# 1_POWER.net
KiCad netlist of a schematic drawn in Altium Designer
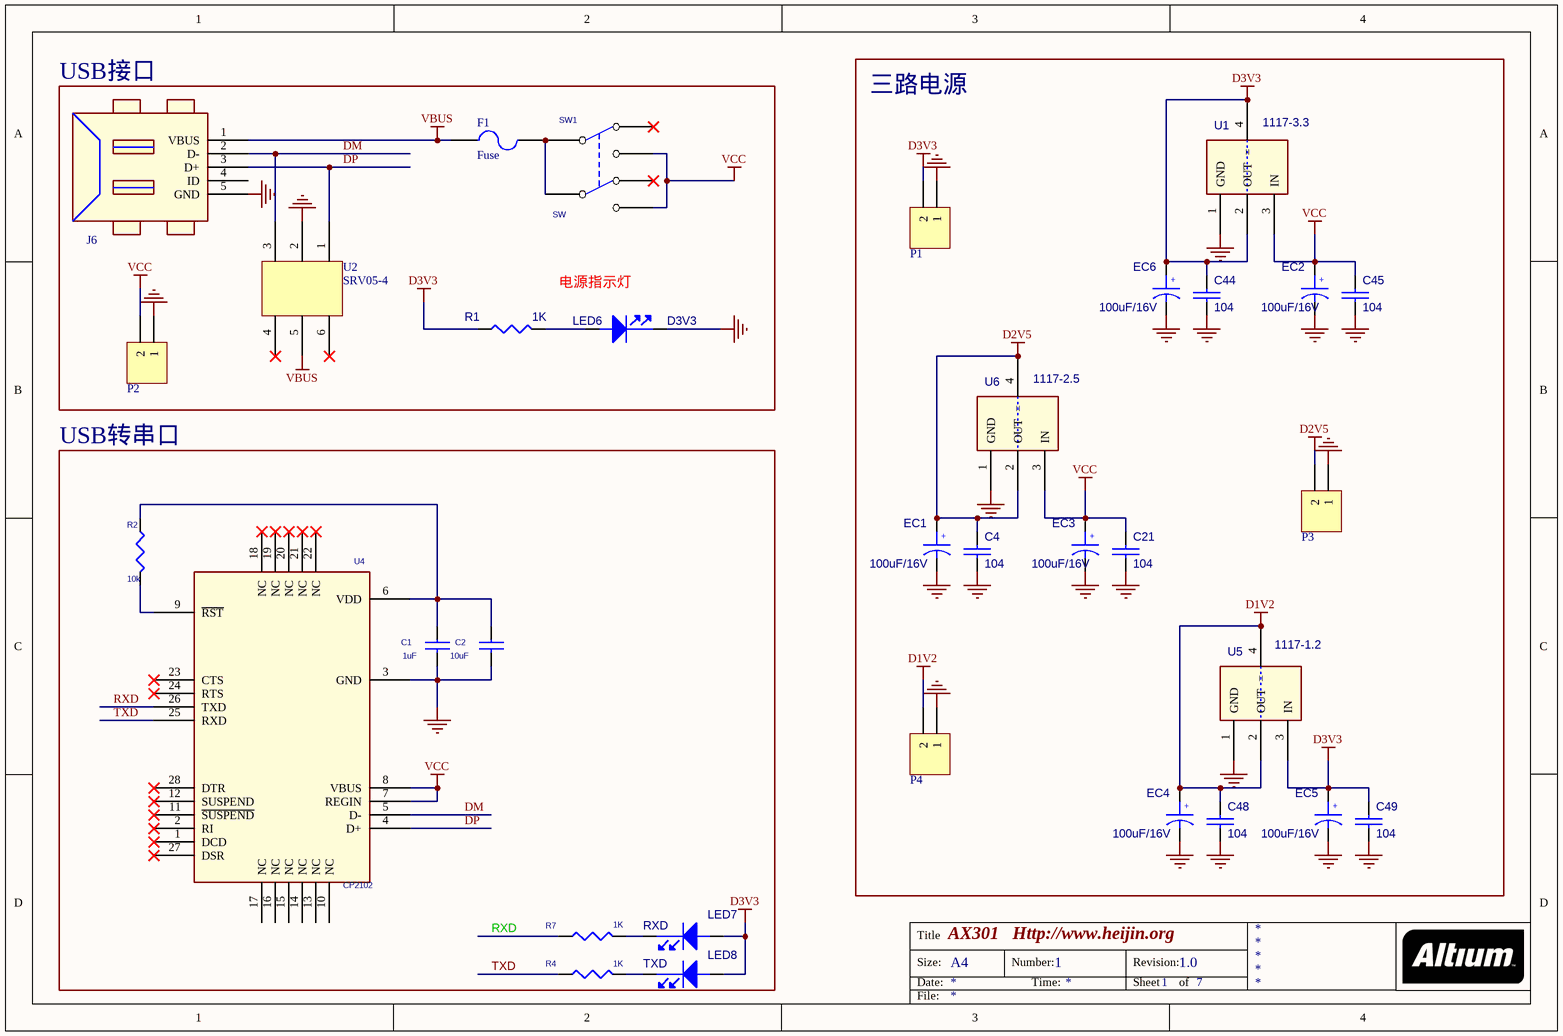
[diagram p0: 1_POWER.SchDoc]

(export (version "E")
  (design (tool "Eeschema 10.0.6"))
  (components
    (comp (ref "C1") (value "1uF") (libsource (lib "*") (part "CAP NP_Dup2")))
    (comp (ref "C2") (value "10uF") (libsource (lib "*") (part "CAP NP_Dup2")))
    (comp (ref "C4") (value "104") (libsource (lib "*") (part "C_Dup4")))
    (comp (ref "C21") (value "104") (libsource (lib "*") (part "C_Dup4")))
    (comp (ref "C44") (value "104") (libsource (lib "*") (part "C_Dup4")))
    (comp (ref "C45") (value "104") (libsource (lib "*") (part "C_Dup4")))
    (comp (ref "C48") (value "104") (libsource (lib "*") (part "C_Dup4")))
    (comp (ref "C49") (value "104") (libsource (lib "*") (part "C_Dup4")))
    (comp (ref "EC1") (value "100uF/16V") (libsource (lib "*") (part "EC")))
    (comp (ref "EC2") (value "100uF/16V") (libsource (lib "*") (part "EC")))
    (comp (ref "EC3") (value "100uF/16V") (libsource (lib "*") (part "EC")))
    (comp (ref "EC4") (value "100uF/16V") (libsource (lib "*") (part "EC")))
    (comp (ref "EC5") (value "100uF/16V") (libsource (lib "*") (part "EC")))
    (comp (ref "EC6") (value "100uF/16V") (libsource (lib "*") (part "EC")))
    (comp (ref "F1")
      (value "Fuse")
      (footprint "ALINX:1812")
      (fields (field (name "PUBLISHER") "Altium Limited"))
      (libsource (lib "Miscellaneous Devices") (part "Fuse 2"))
    )
    (comp (ref "J6") (value "EC2") (footprint "MINIUSBB") (libsource (lib "*") (part "MiniUSBB")))
    (comp (ref "LED6") (value "D3V3") (footprint "LEDSO") (libsource (lib "*") (part "LED_Dup1")))
    (comp (ref "LED7") (value "RXD") (footprint "LEDSO") (libsource (lib "*") (part "LED")))
    (comp (ref "LED8") (value "TXD") (footprint "LEDSO") (libsource (lib "*") (part "LED")))
    (comp (ref "P1")
      (value "3.3V")
      (footprint "HDR1X2")
      (description "Header, 2-Pin")
      (fields (field (name "PUBLISHER") "Altium Limited"))
      (libsource (lib "Miscellaneous Connectors") (part "Header 2"))
    )
    (comp (ref "P2")
      (value "5V")
      (footprint "HDR1X2")
      (description "Header, 2-Pin")
      (fields (field (name "PUBLISHER") "Altium Limited"))
      (libsource (lib "Miscellaneous Connectors") (part "Header 2"))
    )
    (comp (ref "P3")
      (value "3.3V")
      (footprint "HDR1X2")
      (description "Header, 2-Pin")
      (fields (field (name "PUBLISHER") "Altium Limited"))
      (libsource (lib "Miscellaneous Connectors") (part "Header 2"))
    )
    (comp (ref "P4")
      (value "1.2V")
      (footprint "HDR1X2")
      (description "Header, 2-Pin")
      (fields (field (name "PUBLISHER") "Altium Limited"))
      (libsource (lib "Miscellaneous Connectors") (part "Header 2"))
    )
    (comp (ref "R1") (value "1K") (footprint "0603") (libsource (lib "*") (part "R")))
    (comp (ref "R2") (value "10k") (libsource (lib "*") (part "RESISTOR")))
    (comp (ref "R4") (value "1K") (footprint "0603") (libsource (lib "*") (part "R_Dup3")))
    (comp (ref "R7") (value "1K") (footprint "0603") (libsource (lib "*") (part "R_Dup3")))
    (comp (ref "SW1") (value "SW") (libsource (lib "*") (part "SW KEY-DPDT")))
    (comp (ref "U1") (value "1117-3.3") (footprint "SOT223") (libsource (lib "*") (part "1117-3.3")))
    (comp (ref "U2")
      (value "SRV05-4")
      (footprint "wfj_pcb:SOT23-6")
      (libsource (lib "heijin") (part "SRV05-4"))
    )
    (comp (ref "U4") (value "CP2102") (libsource (lib "*") (part "CP2102_0")))
    (comp (ref "U5") (value "1117-1.2") (footprint "SOT223") (libsource (lib "*") (part "1117-3.3")))
    (comp (ref "U6") (value "1117-2.5") (footprint "SOT223") (libsource (lib "*") (part "1117-3.3")))
  )
  (nets
    (net (code "1") (name "/DM") (class "Default")
      (node (ref "J6") (pin "2") (pinfunction "D-_2") (pintype "passive"))
      (node (ref "U2") (pin "3") (pinfunction "3_3") (pintype "passive"))
      (node (ref "U4") (pin "5") (pinfunction "D-_5") (pintype "passive"))
    )
    (net (code "2") (name "/DP") (class "Default")
      (node (ref "J6") (pin "3") (pinfunction "D+_3") (pintype "passive"))
      (node (ref "U2") (pin "1") (pinfunction "1_1") (pintype "passive"))
      (node (ref "U4") (pin "4") (pinfunction "D+_4") (pintype "passive"))
    )
    (net (code "3") (name "/RXD") (class "Default")
      (node (ref "R7") (pin "1") (pinfunction "1_1") (pintype "passive"))
      (node (ref "U4") (pin "26") (pinfunction "TXD_26") (pintype "passive"))
    )
    (net (code "4") (name "/TXD") (class "Default")
      (node (ref "R4") (pin "1") (pinfunction "1_1") (pintype "passive"))
      (node (ref "U4") (pin "25") (pinfunction "RXD_25") (pintype "passive"))
    )
    (net (code "5") (name "D1V2") (class "Default")
      (node (ref "C48") (pin "1") (pinfunction "1_1") (pintype "passive"))
      (node (ref "EC4") (pin "1") (pinfunction "1_1") (pintype "passive"))
      (node (ref "P4") (pin "2") (pinfunction "2_2") (pintype "passive"))
      (node (ref "U5") (pin "2") (pinfunction "OUT_2") (pintype "passive"))
      (node (ref "U5") (pin "4") (pinfunction "=_4") (pintype "passive"))
    )
    (net (code "6") (name "D2V5") (class "Default")
      (node (ref "C4") (pin "1") (pinfunction "1_1") (pintype "passive"))
      (node (ref "EC1") (pin "1") (pinfunction "1_1") (pintype "passive"))
      (node (ref "P3") (pin "2") (pinfunction "2_2") (pintype "passive"))
      (node (ref "U6") (pin "2") (pinfunction "OUT_2") (pintype "passive"))
      (node (ref "U6") (pin "4") (pinfunction "=_4") (pintype "passive"))
    )
    (net (code "7") (name "D3V3") (class "Default")
      (node (ref "C44") (pin "1") (pinfunction "1_1") (pintype "passive"))
      (node (ref "C49") (pin "1") (pinfunction "1_1") (pintype "passive"))
      (node (ref "EC5") (pin "1") (pinfunction "1_1") (pintype "passive"))
      (node (ref "EC6") (pin "1") (pinfunction "1_1") (pintype "passive"))
      (node (ref "LED7") (pin "1") (pinfunction "ANODE_1") (pintype "passive"))
      (node (ref "LED8") (pin "1") (pinfunction "ANODE_1") (pintype "passive"))
      (node (ref "P1") (pin "2") (pinfunction "2_2") (pintype "passive"))
      (node (ref "R1") (pin "1") (pinfunction "1_1") (pintype "passive"))
      (node (ref "U1") (pin "2") (pinfunction "OUT_2") (pintype "passive"))
      (node (ref "U1") (pin "4") (pinfunction "=_4") (pintype "passive"))
      (node (ref "U5") (pin "3") (pinfunction "IN_3") (pintype "passive"))
    )
    (net (code "8") (name "GND") (class "Default")
      (node (ref "C1") (pin "2") (pinfunction "2_2") (pintype "passive"))
      (node (ref "C2") (pin "2") (pinfunction "2_2") (pintype "passive"))
      (node (ref "C21") (pin "2") (pinfunction "2_2") (pintype "passive"))
      (node (ref "C4") (pin "2") (pinfunction "2_2") (pintype "passive"))
      (node (ref "C44") (pin "2") (pinfunction "2_2") (pintype "passive"))
      (node (ref "C45") (pin "2") (pinfunction "2_2") (pintype "passive"))
      (node (ref "C48") (pin "2") (pinfunction "2_2") (pintype "passive"))
      (node (ref "C49") (pin "2") (pinfunction "2_2") (pintype "passive"))
      (node (ref "EC1") (pin "2") (pinfunction "2_2") (pintype "passive"))
      (node (ref "EC2") (pin "2") (pinfunction "2_2") (pintype "passive"))
      (node (ref "EC3") (pin "2") (pinfunction "2_2") (pintype "passive"))
      (node (ref "EC4") (pin "2") (pinfunction "2_2") (pintype "passive"))
      (node (ref "EC5") (pin "2") (pinfunction "2_2") (pintype "passive"))
      (node (ref "EC6") (pin "2") (pinfunction "2_2") (pintype "passive"))
      (node (ref "J6") (pin "5") (pinfunction "GND_5") (pintype "passive"))
      (node (ref "LED6") (pin "2") (pinfunction "CATHODE_2") (pintype "passive"))
      (node (ref "P1") (pin "1") (pinfunction "1_1") (pintype "passive"))
      (node (ref "P2") (pin "1") (pinfunction "1_1") (pintype "passive"))
      (node (ref "P3") (pin "1") (pinfunction "1_1") (pintype "passive"))
      (node (ref "P4") (pin "1") (pinfunction "1_1") (pintype "passive"))
      (node (ref "U1") (pin "1") (pinfunction "GND_1") (pintype "passive"))
      (node (ref "U2") (pin "2") (pinfunction "2_2") (pintype "passive"))
      (node (ref "U4") (pin "3") (pinfunction "GND_3") (pintype "power_in"))
      (node (ref "U5") (pin "1") (pinfunction "GND_1") (pintype "passive"))
      (node (ref "U6") (pin "1") (pinfunction "GND_1") (pintype "passive"))
    )
    (net (code "9") (name "Net-(LED6-ANODE)") (class "Default")
      (node (ref "LED6") (pin "1") (pinfunction "ANODE_1") (pintype "passive"))
      (node (ref "R1") (pin "2") (pinfunction "2_2") (pintype "passive"))
    )
    (net (code "10") (name "Net-(LED7-CATHODE)") (class "Default")
      (node (ref "LED7") (pin "2") (pinfunction "CATHODE_2") (pintype "passive"))
      (node (ref "R7") (pin "2") (pinfunction "2_2") (pintype "passive"))
    )
    (net (code "11") (name "Net-(LED8-CATHODE)") (class "Default")
      (node (ref "LED8") (pin "2") (pinfunction "CATHODE_2") (pintype "passive"))
      (node (ref "R4") (pin "2") (pinfunction "2_2") (pintype "passive"))
    )
    (net (code "12") (name "Net-(SW1-COMMON1)") (class "Default")
      (node (ref "F1") (pin "2") (pinfunction "2_2") (pintype "passive"))
      (node (ref "SW1") (pin "2") (pinfunction "COMMON1_2") (pintype "passive"))
      (node (ref "SW1") (pin "5") (pinfunction "COMMON2_5") (pintype "passive"))
    )
    (net (code "13") (name "Net-(U4-VDD)") (class "Default")
      (node (ref "C1") (pin "1") (pinfunction "1_1") (pintype "passive"))
      (node (ref "C2") (pin "1") (pinfunction "1_1") (pintype "passive"))
      (node (ref "R2") (pin "2") (pinfunction "2_2") (pintype "passive"))
      (node (ref "U4") (pin "6") (pinfunction "VDD_6") (pintype "power_in"))
    )
    (net (code "14") (name "Net-(U4-~{RST})") (class "Default")
      (node (ref "R2") (pin "1") (pinfunction "1_1") (pintype "passive"))
      (node (ref "U4") (pin "9") (pinfunction "~{RST}_9") (pintype "passive"))
    )
    (net (code "15") (name "VBUS") (class "Default")
      (node (ref "F1") (pin "1") (pinfunction "1_1") (pintype "passive"))
      (node (ref "J6") (pin "1") (pinfunction "VBUS_1") (pintype "passive"))
      (node (ref "U2") (pin "5") (pinfunction "5_5") (pintype "passive"))
    )
    (net (code "16") (name "VCC") (class "Default")
      (node (ref "C21") (pin "1") (pinfunction "1_1") (pintype "passive"))
      (node (ref "C45") (pin "1") (pinfunction "1_1") (pintype "passive"))
      (node (ref "EC2") (pin "1") (pinfunction "1_1") (pintype "passive"))
      (node (ref "EC3") (pin "1") (pinfunction "1_1") (pintype "passive"))
      (node (ref "P2") (pin "2") (pinfunction "2_2") (pintype "passive"))
      (node (ref "SW1") (pin "3") (pinfunction "NO1_3") (pintype "passive"))
      (node (ref "SW1") (pin "6") (pinfunction "NO2_6") (pintype "passive"))
      (node (ref "U1") (pin "3") (pinfunction "IN_3") (pintype "passive"))
      (node (ref "U4") (pin "7") (pinfunction "REGIN_7") (pintype "passive"))
      (node (ref "U4") (pin "8") (pinfunction "VBUS_8") (pintype "passive"))
      (node (ref "U6") (pin "3") (pinfunction "IN_3") (pintype "passive"))
    )
    (net (code "17") (name "unconnected-(J6-ID-Pad4)") (class "Default")
      (node (ref "J6") (pin "4") (pinfunction "ID_4") (pintype "passive"))
    )
    (net (code "18") (name "unconnected-(SW1-NC1-Pad1)") (class "Default")
      (node (ref "SW1") (pin "1") (pinfunction "NC1_1") (pintype "passive+no_connect"))
    )
    (net (code "19") (name "unconnected-(SW1-NC2-Pad4)") (class "Default")
      (node (ref "SW1") (pin "4") (pinfunction "NC2_4") (pintype "passive+no_connect"))
    )
    (net (code "20") (name "unconnected-(U2-Pad4)") (class "Default")
      (node (ref "U2") (pin "4") (pinfunction "4_4") (pintype "passive+no_connect"))
    )
    (net (code "21") (name "unconnected-(U2-Pad6)") (class "Default")
      (node (ref "U2") (pin "6") (pinfunction "6_6") (pintype "passive+no_connect"))
    )
    (net (code "22") (name "unconnected-(U4-CTS-Pad23)") (class "Default")
      (node (ref "U4") (pin "23") (pinfunction "CTS_23") (pintype "passive+no_connect"))
    )
    (net (code "23") (name "unconnected-(U4-DCD-Pad1)") (class "Default")
      (node (ref "U4") (pin "1") (pinfunction "DCD_1") (pintype "passive+no_connect"))
    )
    (net (code "24") (name "unconnected-(U4-DSR-Pad27)") (class "Default")
      (node (ref "U4") (pin "27") (pinfunction "DSR_27") (pintype "passive+no_connect"))
    )
    (net (code "25") (name "unconnected-(U4-DTR-Pad28)") (class "Default")
      (node (ref "U4") (pin "28") (pinfunction "DTR_28") (pintype "passive+no_connect"))
    )
    (net (code "26") (name "unconnected-(U4-NC-Pad10)") (class "Default")
      (node (ref "U4") (pin "10") (pinfunction "NC_10") (pintype "passive"))
    )
    (net (code "27") (name "unconnected-(U4-NC-Pad13)") (class "Default")
      (node (ref "U4") (pin "13") (pinfunction "NC_13") (pintype "passive"))
    )
    (net (code "28") (name "unconnected-(U4-NC-Pad14)") (class "Default")
      (node (ref "U4") (pin "14") (pinfunction "NC_14") (pintype "passive"))
    )
    (net (code "29") (name "unconnected-(U4-NC-Pad15)") (class "Default")
      (node (ref "U4") (pin "15") (pinfunction "NC_15") (pintype "passive"))
    )
    (net (code "30") (name "unconnected-(U4-NC-Pad16)") (class "Default")
      (node (ref "U4") (pin "16") (pinfunction "NC_16") (pintype "passive"))
    )
    (net (code "31") (name "unconnected-(U4-NC-Pad17)") (class "Default")
      (node (ref "U4") (pin "17") (pinfunction "NC_17") (pintype "passive"))
    )
    (net (code "32") (name "unconnected-(U4-NC-Pad18)") (class "Default")
      (node (ref "U4") (pin "18") (pinfunction "NC_18") (pintype "passive+no_connect"))
    )
    (net (code "33") (name "unconnected-(U4-NC-Pad19)") (class "Default")
      (node (ref "U4") (pin "19") (pinfunction "NC_19") (pintype "passive+no_connect"))
    )
    (net (code "34") (name "unconnected-(U4-NC-Pad20)") (class "Default")
      (node (ref "U4") (pin "20") (pinfunction "NC_20") (pintype "passive+no_connect"))
    )
    (net (code "35") (name "unconnected-(U4-NC-Pad21)") (class "Default")
      (node (ref "U4") (pin "21") (pinfunction "NC_21") (pintype "passive+no_connect"))
    )
    (net (code "36") (name "unconnected-(U4-NC-Pad22)") (class "Default")
      (node (ref "U4") (pin "22") (pinfunction "NC_22") (pintype "passive+no_connect"))
    )
    (net (code "37") (name "unconnected-(U4-RI-Pad2)") (class "Default")
      (node (ref "U4") (pin "2") (pinfunction "RI_2") (pintype "passive+no_connect"))
    )
    (net (code "38") (name "unconnected-(U4-RTS-Pad24)") (class "Default")
      (node (ref "U4") (pin "24") (pinfunction "RTS_24") (pintype "passive+no_connect"))
    )
    (net (code "39") (name "unconnected-(U4-SUSPEND-Pad12)") (class "Default")
      (node (ref "U4") (pin "12") (pinfunction "SUSPEND_12") (pintype "passive+no_connect"))
    )
    (net (code "40") (name "unconnected-(U4-~{SUSPEND}-Pad11)") (class "Default")
      (node (ref "U4") (pin "11") (pinfunction "~{SUSPEND}_11") (pintype "passive+no_connect"))
    )
  )
)
